# encoder.net
KiCad netlist of a schematic drawn in Altium Designer
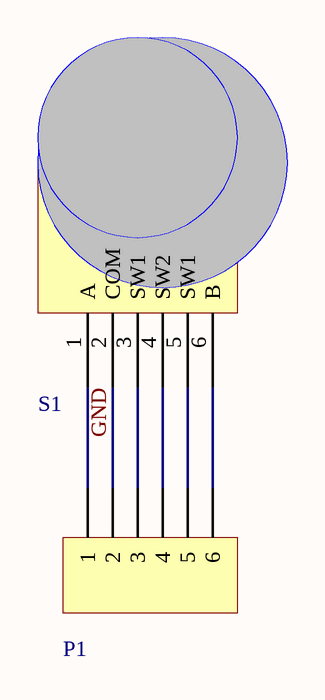
[diagram p0: encoder.SchDoc]

(export (version "E")
  (design (tool "Eeschema 10.0.6"))
  (components
    (comp (ref "P1")
      (value "Header 6")
      (footprint "MX1.25-6P 立")
      (description "Header, 6-Pin")
      (fields (field (name "PUBLISHER") "Altium Limited"))
      (libsource (lib "Miscellaneous Connectors") (part "Header 6"))
    )
    (comp (ref "S1") (value "滚轮编码器") (footprint "滚轮编码器") (libsource (lib "zhjrm") (part "滚轮编码器")))
  )
  (nets
    (net (code "1") (name "/GND") (class "Default")
      (node (ref "P1") (pin "2") (pinfunction "2_2") (pintype "passive"))
      (node (ref "S1") (pin "2") (pinfunction "COM_2") (pintype "passive"))
    )
    (net (code "2") (name "Net-(P1-Pad3)") (class "Default")
      (node (ref "P1") (pin "3") (pinfunction "3_3") (pintype "passive"))
      (node (ref "S1") (pin "3") (pinfunction "SW1_3") (pintype "passive"))
    )
    (net (code "3") (name "Net-(P1-Pad5)") (class "Default")
      (node (ref "P1") (pin "5") (pinfunction "5_5") (pintype "passive"))
      (node (ref "S1") (pin "5") (pinfunction "SW1_5") (pintype "passive"))
    )
    (net (code "4") (name "Net-(S1-A)") (class "Default")
      (node (ref "P1") (pin "1") (pinfunction "1_1") (pintype "passive"))
      (node (ref "S1") (pin "1") (pinfunction "A_1") (pintype "passive"))
    )
    (net (code "5") (name "Net-(S1-B)") (class "Default")
      (node (ref "P1") (pin "6") (pinfunction "6_6") (pintype "passive"))
      (node (ref "S1") (pin "6") (pinfunction "B_6") (pintype "passive"))
    )
    (net (code "6") (name "Net-(S1-SW2)") (class "Default")
      (node (ref "P1") (pin "4") (pinfunction "4_4") (pintype "passive"))
      (node (ref "S1") (pin "4") (pinfunction "SW2_4") (pintype "passive"))
    )
  )
)
